# Connectors.net
KiCad netlist of a schematic drawn in Altium Designer
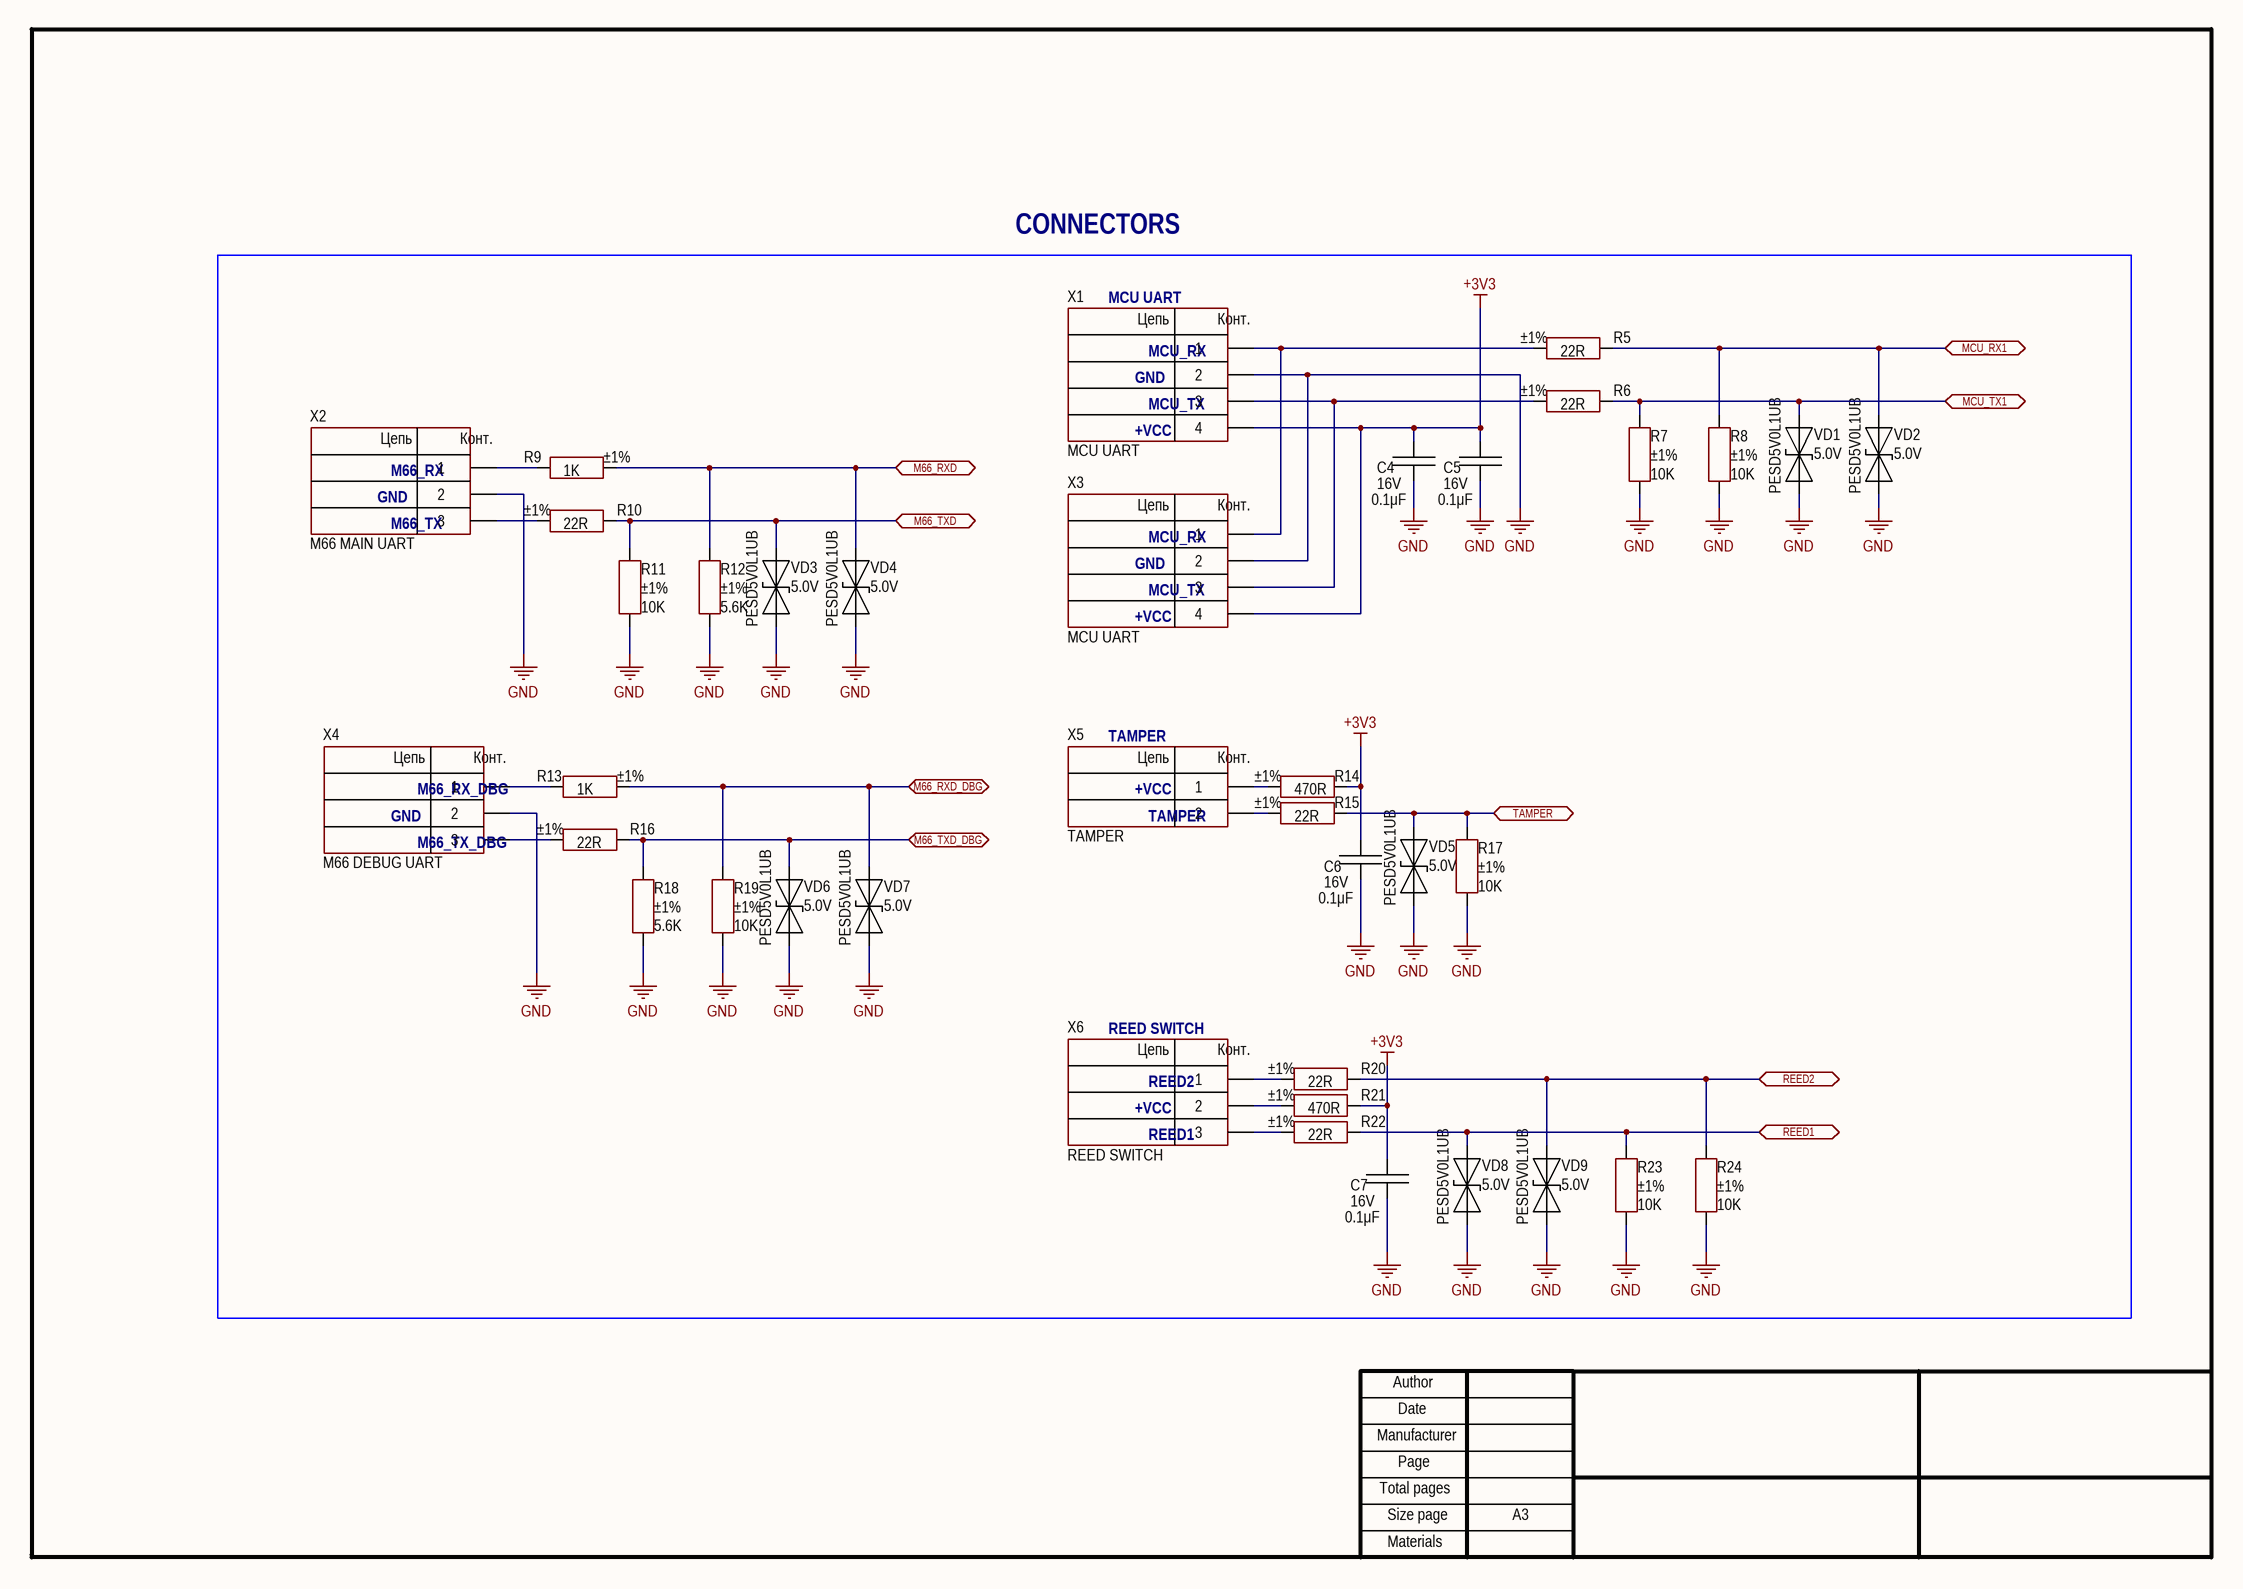
[diagram p0: Connectors.SchDoc]

(export (version "E")
  (design (tool "Eeschema 10.0.6"))
  (components
    (comp (ref "C4")
      (value "0.1μF")
      (footprint "CAP: 0402")
      (description "±10% 16V Ceramic Capacitor X7R 0402 (1005 Metric)")
      (fields
        (field (name "MANUFACTURER") "Yageo")
        (field (name "PARTNUMBER") "CC0402KRX7R7BB104")
        (field (name "VOLTAGE") "16V")
      )
      (libsource (lib "capacitor") (part "Ceramic_0402"))
    )
    (comp (ref "C5")
      (value "0.1μF")
      (footprint "CAP: 0402")
      (description "±10% 16V Ceramic Capacitor X7R 0402 (1005 Metric)")
      (fields
        (field (name "MANUFACTURER") "Yageo")
        (field (name "PARTNUMBER") "CC0402KRX7R7BB104")
        (field (name "VOLTAGE") "16V")
      )
      (libsource (lib "capacitor") (part "Ceramic_0402"))
    )
    (comp (ref "C6")
      (value "0.1μF")
      (footprint "CAP: 0402")
      (description "±10% 16V Ceramic Capacitor X7R 0402 (1005 Metric)")
      (fields
        (field (name "MANUFACTURER") "Yageo")
        (field (name "PARTNUMBER") "CC0402KRX7R7BB104")
        (field (name "VOLTAGE") "16V")
      )
      (libsource (lib "capacitor") (part "Ceramic_0402"))
    )
    (comp (ref "C7")
      (value "0.1μF")
      (footprint "CAP: 0402")
      (description "±10% 16V Ceramic Capacitor X7R 0402 (1005 Metric)")
      (fields
        (field (name "MANUFACTURER") "Yageo")
        (field (name "PARTNUMBER") "CC0402KRX7R7BB104")
        (field (name "VOLTAGE") "16V")
      )
      (libsource (lib "capacitor") (part "Ceramic_0402"))
    )
    (comp (ref "R5")
      (value "22R")
      (footprint "RES: 0402")
      (description "22 Ohms ±1% 0.063W, 1/16W Chip Resistor 0402 (1005 Metric) Moisture Resistant Thick Film")
      (fields
        (field (name "MANUFACTURER") "Yageo")
        (field (name "PARTNUMBER") "RC0402FR-0722RL")
        (field (name "TOLERANCE") "±1%")
      )
      (libsource (lib "resistor") (part "Resistor_0402"))
    )
    (comp (ref "R6")
      (value "22R")
      (footprint "RES: 0402")
      (description "22 Ohms ±1% 0.063W, 1/16W Chip Resistor 0402 (1005 Metric) Moisture Resistant Thick Film")
      (fields
        (field (name "MANUFACTURER") "Yageo")
        (field (name "PARTNUMBER") "RC0402FR-0722RL")
        (field (name "TOLERANCE") "±1%")
      )
      (libsource (lib "resistor") (part "Resistor_0402"))
    )
    (comp (ref "R7")
      (value "10K")
      (footprint "RES: 0402")
      (description "10 kOhms ±1% 0.063W, 1/16W Chip Resistor 0402 (1005 Metric) Moisture Resistant Thick Film")
      (fields
        (field (name "MANUFACTURER") "Yageo")
        (field (name "PARTNUMBER") "RC0402FR-0710KL")
        (field (name "TOLERANCE") "±1%")
      )
      (libsource (lib "") (part "Resistor_0402_1"))
    )
    (comp (ref "R8")
      (value "10K")
      (footprint "RES: 0402")
      (description "10 kOhms ±1% 0.063W, 1/16W Chip Resistor 0402 (1005 Metric) Moisture Resistant Thick Film")
      (fields
        (field (name "MANUFACTURER") "Yageo")
        (field (name "PARTNUMBER") "RC0402FR-0710KL")
        (field (name "TOLERANCE") "±1%")
      )
      (libsource (lib "") (part "Resistor_0402_1"))
    )
    (comp (ref "R9")
      (value "1K")
      (footprint "RES: 0402")
      (description "1 kOhms ±1% 0.063W, 1/16W Chip Resistor 0402 (1005 Metric) Moisture Resistant Thick Film")
      (fields
        (field (name "MANUFACTURER") "Yageo")
        (field (name "PARTNUMBER") "RC0402FR-071KP")
        (field (name "TOLERANCE") "±1%")
      )
      (libsource (lib "resistor") (part "Resistor_0402"))
    )
    (comp (ref "R10")
      (value "22R")
      (footprint "RES: 0402")
      (description "22 Ohms ±1% 0.063W, 1/16W Chip Resistor 0402 (1005 Metric) Moisture Resistant Thick Film")
      (fields
        (field (name "MANUFACTURER") "Yageo")
        (field (name "PARTNUMBER") "RC0402FR-0722RL")
        (field (name "TOLERANCE") "±1%")
      )
      (libsource (lib "resistor") (part "Resistor_0402"))
    )
    (comp (ref "R11")
      (value "10K")
      (footprint "RES: 0402")
      (description "10 kOhms ±1% 0.063W, 1/16W Chip Resistor 0402 (1005 Metric) Moisture Resistant Thick Film")
      (fields
        (field (name "MANUFACTURER") "Yageo")
        (field (name "PARTNUMBER") "RC0402FR-0710KL")
        (field (name "TOLERANCE") "±1%")
      )
      (libsource (lib "resistor") (part "Resistor_0402"))
    )
    (comp (ref "R12")
      (value "5.6K")
      (footprint "RES: 0402")
      (description "5.6 kOhms ±1% 0.063W, 1/16W Chip Resistor 0402 (1005 Metric) Moisture Resistant Thick Film")
      (fields
        (field (name "MANUFACTURER") "Yageo")
        (field (name "PARTNUMBER") "RC0402FR-075K6L")
        (field (name "TOLERANCE") "±1%")
      )
      (libsource (lib "") (part "Resistor_0402_2"))
    )
    (comp (ref "R13")
      (value "1K")
      (footprint "RES: 0402")
      (description "1 kOhms ±1% 0.063W, 1/16W Chip Resistor 0402 (1005 Metric) Moisture Resistant Thick Film")
      (fields
        (field (name "MANUFACTURER") "Yageo")
        (field (name "PARTNUMBER") "RC0402FR-071KP")
        (field (name "TOLERANCE") "±1%")
      )
      (libsource (lib "resistor") (part "Resistor_0402"))
    )
    (comp (ref "R14")
      (value "470R")
      (footprint "RES: 0402")
      (description "220 Ohms ±1% 0.063W, 1/16W Chip Resistor 0402 (1005 Metric) Moisture Resistant Thick Film")
      (fields
        (field (name "MANUFACTURER") "Yageo")
        (field (name "PARTNUMBER") "RC0402FR-07470RL")
        (field (name "TOLERANCE") "±1%")
      )
      (libsource (lib "") (part "Resistor_0402_1"))
    )
    (comp (ref "R15")
      (value "22R")
      (footprint "RES: 0402")
      (description "22 Ohms ±1% 0.063W, 1/16W Chip Resistor 0402 (1005 Metric) Moisture Resistant Thick Film")
      (fields
        (field (name "MANUFACTURER") "Yageo")
        (field (name "PARTNUMBER") "RC0402FR-0722RL")
        (field (name "TOLERANCE") "±1%")
      )
      (libsource (lib "resistor") (part "Resistor_0402"))
    )
    (comp (ref "R16")
      (value "22R")
      (footprint "RES: 0402")
      (description "22 Ohms ±1% 0.063W, 1/16W Chip Resistor 0402 (1005 Metric) Moisture Resistant Thick Film")
      (fields
        (field (name "MANUFACTURER") "Yageo")
        (field (name "PARTNUMBER") "RC0402FR-0722RL")
        (field (name "TOLERANCE") "±1%")
      )
      (libsource (lib "resistor") (part "Resistor_0402"))
    )
    (comp (ref "R17")
      (value "10K")
      (footprint "RES: 0402")
      (description "10 kOhms ±1% 0.063W, 1/16W Chip Resistor 0402 (1005 Metric) Moisture Resistant Thick Film")
      (fields
        (field (name "MANUFACTURER") "Yageo")
        (field (name "PARTNUMBER") "RC0402FR-0710KL")
        (field (name "TOLERANCE") "±1%")
      )
      (libsource (lib "resistor") (part "Resistor_0402"))
    )
    (comp (ref "R18")
      (value "5.6K")
      (footprint "RES: 0402")
      (description "5.6 kOhms ±1% 0.063W, 1/16W Chip Resistor 0402 (1005 Metric) Moisture Resistant Thick Film")
      (fields
        (field (name "MANUFACTURER") "Yageo")
        (field (name "PARTNUMBER") "RC0402FR-075K6L")
        (field (name "TOLERANCE") "±1%")
      )
      (libsource (lib "") (part "Resistor_0402_2"))
    )
    (comp (ref "R19")
      (value "10K")
      (footprint "RES: 0402")
      (description "10 kOhms ±1% 0.063W, 1/16W Chip Resistor 0402 (1005 Metric) Moisture Resistant Thick Film")
      (fields
        (field (name "MANUFACTURER") "Yageo")
        (field (name "PARTNUMBER") "RC0402FR-0710KL")
        (field (name "TOLERANCE") "±1%")
      )
      (libsource (lib "resistor") (part "Resistor_0402"))
    )
    (comp (ref "R20")
      (value "22R")
      (footprint "RES: 0402")
      (description "22 Ohms ±1% 0.063W, 1/16W Chip Resistor 0402 (1005 Metric) Moisture Resistant Thick Film")
      (fields
        (field (name "MANUFACTURER") "Yageo")
        (field (name "PARTNUMBER") "RC0402FR-0722RL")
        (field (name "TOLERANCE") "±1%")
      )
      (libsource (lib "resistor") (part "Resistor_0402"))
    )
    (comp (ref "R21")
      (value "470R")
      (footprint "RES: 0402")
      (description "220 Ohms ±1% 0.063W, 1/16W Chip Resistor 0402 (1005 Metric) Moisture Resistant Thick Film")
      (fields
        (field (name "MANUFACTURER") "Yageo")
        (field (name "PARTNUMBER") "RC0402FR-07470RL")
        (field (name "TOLERANCE") "±1%")
      )
      (libsource (lib "") (part "Resistor_0402_1"))
    )
    (comp (ref "R22")
      (value "22R")
      (footprint "RES: 0402")
      (description "22 Ohms ±1% 0.063W, 1/16W Chip Resistor 0402 (1005 Metric) Moisture Resistant Thick Film")
      (fields
        (field (name "MANUFACTURER") "Yageo")
        (field (name "PARTNUMBER") "RC0402FR-0722RL")
        (field (name "TOLERANCE") "±1%")
      )
      (libsource (lib "resistor") (part "Resistor_0402"))
    )
    (comp (ref "R23")
      (value "10K")
      (footprint "RES: 0402")
      (description "10 kOhms ±1% 0.063W, 1/16W Chip Resistor 0402 (1005 Metric) Moisture Resistant Thick Film")
      (fields
        (field (name "MANUFACTURER") "Yageo")
        (field (name "PARTNUMBER") "RC0402FR-0710KL")
        (field (name "TOLERANCE") "±1%")
      )
      (libsource (lib "resistor") (part "Resistor_0402"))
    )
    (comp (ref "R24")
      (value "10K")
      (footprint "RES: 0402")
      (description "10 kOhms ±1% 0.063W, 1/16W Chip Resistor 0402 (1005 Metric) Moisture Resistant Thick Film")
      (fields
        (field (name "MANUFACTURER") "Yageo")
        (field (name "PARTNUMBER") "RC0402FR-0710KL")
        (field (name "TOLERANCE") "±1%")
      )
      (libsource (lib "resistor") (part "Resistor_0402"))
    )
    (comp (ref "VD1")
      (value "~")
      (footprint "DIODE: SOD523")
      (description "12V Clamp 3.5A (8/20µs) Ipp Tvs Diode Surface Mount SOD-523")
      (fields
        (field (name "MANUFACTURER") "Nexperia")
        (field (name "VALUEMANUFACTURERPARTNUMBER") "ESD TVS diode, 5.0V, 3.5A, , , SOD-523, -55...+150°C")
        (field (name "VOLTAGE") "5.0V")
        (field (name "PARTNUMBER") "PESD5V0L1UB")
      )
      (libsource (lib "diode") (part "TVS_single"))
    )
    (comp (ref "VD2")
      (value "~")
      (footprint "DIODE: SOD523")
      (description "12V Clamp 3.5A (8/20µs) Ipp Tvs Diode Surface Mount SOD-523")
      (fields
        (field (name "MANUFACTURER") "Nexperia")
        (field (name "VALUEMANUFACTURERPARTNUMBER") "ESD TVS diode, 5.0V, 3.5A, , , SOD-523, -55...+150°C")
        (field (name "VOLTAGE") "5.0V")
        (field (name "PARTNUMBER") "PESD5V0L1UB")
      )
      (libsource (lib "diode") (part "TVS_single"))
    )
    (comp (ref "VD3")
      (value "~")
      (footprint "DIODE: SOD523")
      (description "12V Clamp 3.5A (8/20µs) Ipp Tvs Diode Surface Mount SOD-523")
      (fields
        (field (name "MANUFACTURER") "Nexperia")
        (field (name "VALUEMANUFACTURERPARTNUMBER") "ESD TVS diode, 5.0V, 3.5A, , , SOD-523, -55...+150°C")
        (field (name "VOLTAGE") "5.0V")
        (field (name "PARTNUMBER") "PESD5V0L1UB")
      )
      (libsource (lib "diode") (part "TVS_single"))
    )
    (comp (ref "VD4")
      (value "~")
      (footprint "DIODE: SOD523")
      (description "12V Clamp 3.5A (8/20µs) Ipp Tvs Diode Surface Mount SOD-523")
      (fields
        (field (name "MANUFACTURER") "Nexperia")
        (field (name "VALUEMANUFACTURERPARTNUMBER") "ESD TVS diode, 5.0V, 3.5A, , , SOD-523, -55...+150°C")
        (field (name "VOLTAGE") "5.0V")
        (field (name "PARTNUMBER") "PESD5V0L1UB")
      )
      (libsource (lib "diode") (part "TVS_single"))
    )
    (comp (ref "VD5")
      (value "~")
      (footprint "DIODE: SOD523")
      (description "12V Clamp 3.5A (8/20µs) Ipp Tvs Diode Surface Mount SOD-523")
      (fields
        (field (name "MANUFACTURER") "Nexperia")
        (field (name "VALUEMANUFACTURERPARTNUMBER") "ESD TVS diode, 5.0V, 3.5A, , , SOD-523, -55...+150°C")
        (field (name "VOLTAGE") "5.0V")
        (field (name "PARTNUMBER") "PESD5V0L1UB")
      )
      (libsource (lib "diode") (part "TVS_single"))
    )
    (comp (ref "VD6")
      (value "~")
      (footprint "DIODE: SOD523")
      (description "12V Clamp 3.5A (8/20µs) Ipp Tvs Diode Surface Mount SOD-523")
      (fields
        (field (name "MANUFACTURER") "Nexperia")
        (field (name "VALUEMANUFACTURERPARTNUMBER") "ESD TVS diode, 5.0V, 3.5A, , , SOD-523, -55...+150°C")
        (field (name "VOLTAGE") "5.0V")
        (field (name "PARTNUMBER") "PESD5V0L1UB")
      )
      (libsource (lib "diode") (part "TVS_single"))
    )
    (comp (ref "VD7")
      (value "~")
      (footprint "DIODE: SOD523")
      (description "12V Clamp 3.5A (8/20µs) Ipp Tvs Diode Surface Mount SOD-523")
      (fields
        (field (name "MANUFACTURER") "Nexperia")
        (field (name "VALUEMANUFACTURERPARTNUMBER") "ESD TVS diode, 5.0V, 3.5A, , , SOD-523, -55...+150°C")
        (field (name "VOLTAGE") "5.0V")
        (field (name "PARTNUMBER") "PESD5V0L1UB")
      )
      (libsource (lib "diode") (part "TVS_single"))
    )
    (comp (ref "VD8")
      (value "~")
      (footprint "DIODE: SOD523")
      (description "12V Clamp 3.5A (8/20µs) Ipp Tvs Diode Surface Mount SOD-523")
      (fields
        (field (name "MANUFACTURER") "Nexperia")
        (field (name "VALUEMANUFACTURERPARTNUMBER") "ESD TVS diode, 5.0V, 3.5A, , , SOD-523, -55...+150°C")
        (field (name "VOLTAGE") "5.0V")
        (field (name "PARTNUMBER") "PESD5V0L1UB")
      )
      (libsource (lib "diode") (part "TVS_single"))
    )
    (comp (ref "VD9")
      (value "~")
      (footprint "DIODE: SOD523")
      (description "12V Clamp 3.5A (8/20µs) Ipp Tvs Diode Surface Mount SOD-523")
      (fields
        (field (name "MANUFACTURER") "Nexperia")
        (field (name "VALUEMANUFACTURERPARTNUMBER") "ESD TVS diode, 5.0V, 3.5A, , , SOD-523, -55...+150°C")
        (field (name "VOLTAGE") "5.0V")
        (field (name "PARTNUMBER") "PESD5V0L1UB")
      )
      (libsource (lib "diode") (part "TVS_single"))
    )
    (comp (ref "X1")
      (value "~")
      (footprint "CON: PLS-4")
      (description "Pin Header 4 pin Straight, 2.54mm Through Hole.")
      (fields
        (field (name "MANUFACTURER") "KLS")
        (field (name "VALUEMANUFACTURERPARTNUMBER") "Connector, 4pin, 2.54mm, 500VAC, 3A")
        (field (name "COMMENTTEXT") "MCU UART")
      )
      (libsource (lib "connector") (part "PLS-4"))
    )
    (comp (ref "X2")
      (value "~")
      (footprint "CON: PLS-3")
      (description "Pin Header 3 pin Straight, 2.54mm Through Hole.")
      (fields
        (field (name "MANUFACTURER") "KLS")
        (field (name "VALUEMANUFACTURERPARTNUMBER") "Connector, 3pin, 2.54mm, 500VAC, 3A")
        (field (name "COMMENTTEXT") "M66 MAIN UART")
      )
      (libsource (lib "connector") (part "PLS-3"))
    )
    (comp (ref "X3")
      (value "~")
      (footprint "CON: PLS-4")
      (description "Pin Header 4 pin Straight, 2.54mm Through Hole.")
      (fields
        (field (name "MANUFACTURER") "KLS")
        (field (name "VALUEMANUFACTURERPARTNUMBER") "Connector, 4pin, 2.54mm, 500VAC, 3A")
        (field (name "COMMENTTEXT") "MCU UART")
      )
      (libsource (lib "connector") (part "PLS-4"))
    )
    (comp (ref "X4")
      (value "~")
      (footprint "CON: PLS-3")
      (description "Pin Header 3 pin Straight, 2.54mm Through Hole.")
      (fields
        (field (name "MANUFACTURER") "KLS")
        (field (name "VALUEMANUFACTURERPARTNUMBER") "Connector, 3pin, 2.54mm, 500VAC, 3A")
        (field (name "COMMENTTEXT") "M66 DEBUG UART")
      )
      (libsource (lib "connector") (part "PLS-3"))
    )
    (comp (ref "X5")
      (value "~")
      (footprint "CON: PLS-2")
      (description "Pin Header 2 pin Straight, 2.54mm Through Hole.")
      (fields
        (field (name "MANUFACTURER") "KLS")
        (field (name "VALUEMANUFACTURERPARTNUMBER") "Connector, 2pin, 2.54mm, 500VAC, 3A")
        (field (name "COMMENTTEXT") "TAMPER")
      )
      (libsource (lib "connector") (part "PLS-2"))
    )
    (comp (ref "X6")
      (value "~")
      (footprint "CON: 282834-3")
      (description "3 Position Wire to Board Terminal Block Horizontal with Board 0.100\" (2.54mm) Through Hole")
      (fields
        (field (name "MANUFACTURER") "KLS")
        (field (name "VALUEMANUFACTURERPARTNUMBER") "Block Terminal, 3pin, , 500VAC, 15A")
        (field (name "COMMENTTEXT") "REED SWITCH")
      )
      (libsource (lib "MyLib") (part "KLS2-308V-2.54-03P-4S"))
    )
  )
  (nets
    (net (code "1") (name "+3V3") (class "Default")
      (node (ref "C4") (pin "1") (pinfunction "1_1") (pintype "passive"))
      (node (ref "C5") (pin "1") (pinfunction "1_1") (pintype "passive"))
      (node (ref "C6") (pin "1") (pinfunction "1_1") (pintype "passive"))
      (node (ref "C7") (pin "1") (pinfunction "1_1") (pintype "passive"))
      (node (ref "R14") (pin "1") (pinfunction "1_1") (pintype "passive"))
      (node (ref "R21") (pin "1") (pinfunction "1_1") (pintype "passive"))
      (node (ref "X1") (pin "4") (pinfunction "4_4") (pintype "power_in"))
      (node (ref "X3") (pin "4") (pinfunction "4_4") (pintype "power_in"))
    )
    (net (code "2") (name "/M66_RXD") (class "Default")
      (node (ref "R12") (pin "2") (pinfunction "2_2") (pintype "passive"))
      (node (ref "R9") (pin "2") (pinfunction "2_2") (pintype "passive"))
      (node (ref "VD4") (pin "2") (pinfunction "C_2") (pintype "passive"))
    )
    (net (code "3") (name "/M66_RXD_DBG") (class "Default")
      (node (ref "R13") (pin "2") (pinfunction "2_2") (pintype "passive"))
      (node (ref "R19") (pin "2") (pinfunction "2_2") (pintype "passive"))
      (node (ref "VD7") (pin "2") (pinfunction "C_2") (pintype "passive"))
    )
    (net (code "4") (name "/M66_TXD") (class "Default")
      (node (ref "R10") (pin "2") (pinfunction "2_2") (pintype "passive"))
      (node (ref "R11") (pin "2") (pinfunction "2_2") (pintype "passive"))
      (node (ref "VD3") (pin "2") (pinfunction "C_2") (pintype "passive"))
    )
    (net (code "5") (name "/M66_TXD_DBG") (class "Default")
      (node (ref "R16") (pin "2") (pinfunction "2_2") (pintype "passive"))
      (node (ref "R18") (pin "2") (pinfunction "2_2") (pintype "passive"))
      (node (ref "VD6") (pin "2") (pinfunction "C_2") (pintype "passive"))
    )
    (net (code "6") (name "/MCU_RX1") (class "Default")
      (node (ref "R5") (pin "2") (pinfunction "2_2") (pintype "passive"))
      (node (ref "R8") (pin "1") (pinfunction "1_1") (pintype "passive"))
      (node (ref "VD2") (pin "2") (pinfunction "C_2") (pintype "passive"))
    )
    (net (code "7") (name "/MCU_TX1") (class "Default")
      (node (ref "R6") (pin "2") (pinfunction "2_2") (pintype "passive"))
      (node (ref "R7") (pin "1") (pinfunction "1_1") (pintype "passive"))
      (node (ref "VD1") (pin "2") (pinfunction "C_2") (pintype "passive"))
    )
    (net (code "8") (name "/REED1") (class "Default")
      (node (ref "R22") (pin "2") (pinfunction "2_2") (pintype "passive"))
      (node (ref "R23") (pin "2") (pinfunction "2_2") (pintype "passive"))
      (node (ref "VD8") (pin "2") (pinfunction "C_2") (pintype "passive"))
    )
    (net (code "9") (name "/REED2") (class "Default")
      (node (ref "R20") (pin "2") (pinfunction "2_2") (pintype "passive"))
      (node (ref "R24") (pin "2") (pinfunction "2_2") (pintype "passive"))
      (node (ref "VD9") (pin "2") (pinfunction "C_2") (pintype "passive"))
    )
    (net (code "10") (name "/TAMPER") (class "Default")
      (node (ref "R15") (pin "2") (pinfunction "2_2") (pintype "passive"))
      (node (ref "R17") (pin "2") (pinfunction "2_2") (pintype "passive"))
      (node (ref "VD5") (pin "2") (pinfunction "C_2") (pintype "passive"))
    )
    (net (code "11") (name "GND") (class "Default")
      (node (ref "C4") (pin "2") (pinfunction "2_2") (pintype "passive"))
      (node (ref "C5") (pin "2") (pinfunction "2_2") (pintype "passive"))
      (node (ref "C6") (pin "2") (pinfunction "2_2") (pintype "passive"))
      (node (ref "C7") (pin "2") (pinfunction "2_2") (pintype "passive"))
      (node (ref "R11") (pin "1") (pinfunction "1_1") (pintype "passive"))
      (node (ref "R12") (pin "1") (pinfunction "1_1") (pintype "passive"))
      (node (ref "R17") (pin "1") (pinfunction "1_1") (pintype "passive"))
      (node (ref "R18") (pin "1") (pinfunction "1_1") (pintype "passive"))
      (node (ref "R19") (pin "1") (pinfunction "1_1") (pintype "passive"))
      (node (ref "R23") (pin "1") (pinfunction "1_1") (pintype "passive"))
      (node (ref "R24") (pin "1") (pinfunction "1_1") (pintype "passive"))
      (node (ref "R7") (pin "2") (pinfunction "2_2") (pintype "passive"))
      (node (ref "R8") (pin "2") (pinfunction "2_2") (pintype "passive"))
      (node (ref "VD1") (pin "1") (pinfunction "A_1") (pintype "passive"))
      (node (ref "VD2") (pin "1") (pinfunction "A_1") (pintype "passive"))
      (node (ref "VD3") (pin "1") (pinfunction "A_1") (pintype "passive"))
      (node (ref "VD4") (pin "1") (pinfunction "A_1") (pintype "passive"))
      (node (ref "VD5") (pin "1") (pinfunction "A_1") (pintype "passive"))
      (node (ref "VD6") (pin "1") (pinfunction "A_1") (pintype "passive"))
      (node (ref "VD7") (pin "1") (pinfunction "A_1") (pintype "passive"))
      (node (ref "VD8") (pin "1") (pinfunction "A_1") (pintype "passive"))
      (node (ref "VD9") (pin "1") (pinfunction "A_1") (pintype "passive"))
      (node (ref "X1") (pin "2") (pinfunction "2_2") (pintype "passive"))
      (node (ref "X2") (pin "2") (pinfunction "2_2") (pintype "passive"))
      (node (ref "X3") (pin "2") (pinfunction "2_2") (pintype "passive"))
      (node (ref "X4") (pin "2") (pinfunction "2_2") (pintype "passive"))
    )
    (net (code "12") (name "Net-(R5-Pad1)") (class "Default")
      (node (ref "R5") (pin "1") (pinfunction "1_1") (pintype "passive"))
      (node (ref "X1") (pin "1") (pinfunction "1_1") (pintype "passive"))
      (node (ref "X3") (pin "1") (pinfunction "1_1") (pintype "passive"))
    )
    (net (code "13") (name "Net-(R6-Pad1)") (class "Default")
      (node (ref "R6") (pin "1") (pinfunction "1_1") (pintype "passive"))
      (node (ref "X1") (pin "3") (pinfunction "3_3") (pintype "power_in"))
      (node (ref "X3") (pin "3") (pinfunction "3_3") (pintype "power_in"))
    )
    (net (code "14") (name "Net-(R9-Pad1)") (class "Default")
      (node (ref "R9") (pin "1") (pinfunction "1_1") (pintype "passive"))
      (node (ref "X2") (pin "1") (pinfunction "1_1") (pintype "passive"))
    )
    (net (code "15") (name "Net-(R10-Pad1)") (class "Default")
      (node (ref "R10") (pin "1") (pinfunction "1_1") (pintype "passive"))
      (node (ref "X2") (pin "3") (pinfunction "3_3") (pintype "power_in"))
    )
    (net (code "16") (name "Net-(R13-Pad1)") (class "Default")
      (node (ref "R13") (pin "1") (pinfunction "1_1") (pintype "passive"))
      (node (ref "X4") (pin "1") (pinfunction "1_1") (pintype "passive"))
    )
    (net (code "17") (name "Net-(R14-Pad2)") (class "Default")
      (node (ref "R14") (pin "2") (pinfunction "2_2") (pintype "passive"))
      (node (ref "X5") (pin "1") (pinfunction "1_1") (pintype "passive"))
    )
    (net (code "18") (name "Net-(R15-Pad1)") (class "Default")
      (node (ref "R15") (pin "1") (pinfunction "1_1") (pintype "passive"))
      (node (ref "X5") (pin "2") (pinfunction "2_2") (pintype "passive"))
    )
    (net (code "19") (name "Net-(R16-Pad1)") (class "Default")
      (node (ref "R16") (pin "1") (pinfunction "1_1") (pintype "passive"))
      (node (ref "X4") (pin "3") (pinfunction "3_3") (pintype "power_in"))
    )
    (net (code "20") (name "Net-(R20-Pad1)") (class "Default")
      (node (ref "R20") (pin "1") (pinfunction "1_1") (pintype "passive"))
      (node (ref "X6") (pin "1") (pinfunction "1_1") (pintype "passive"))
    )
    (net (code "21") (name "Net-(R21-Pad2)") (class "Default")
      (node (ref "R21") (pin "2") (pinfunction "2_2") (pintype "passive"))
      (node (ref "X6") (pin "2") (pinfunction "2_2") (pintype "passive"))
    )
    (net (code "22") (name "Net-(R22-Pad1)") (class "Default")
      (node (ref "R22") (pin "1") (pinfunction "1_1") (pintype "passive"))
      (node (ref "X6") (pin "3") (pinfunction "3_3") (pintype "passive"))
    )
  )
)
